# pcb_heater.net
KiCad netlist of a schematic drawn in Altium Designer
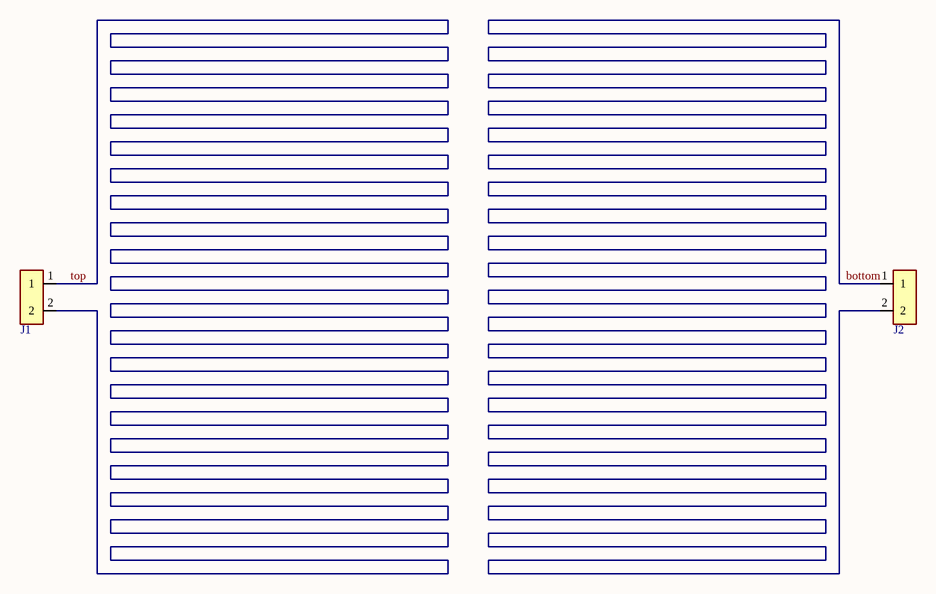
[diagram p0: pcb_heater.SchDoc]

(export (version "E")
  (design (tool "Eeschema 10.0.6"))
  (components
    (comp (ref "J1")
      (value "Connector, PCB heater")
      (footprint "pcb_heater_connector")
      (libsource (lib "") (part "Connector, PCB heater_1"))
    )
    (comp (ref "J2")
      (value "Connector, PCB heater")
      (footprint "pcb_heater_connector")
      (libsource (lib "jclib") (part "Connector, PCB heater"))
    )
  )
  (nets
    (net (code "1") (name "/bottom") (class "Default")
      (node (ref "J2") (pin "1") (pinfunction "1_1") (pintype "passive"))
      (node (ref "J2") (pin "2") (pinfunction "2_2") (pintype "passive"))
    )
    (net (code "2") (name "/top") (class "Default")
      (node (ref "J1") (pin "1") (pinfunction "1_1") (pintype "passive"))
      (node (ref "J1") (pin "2") (pinfunction "2_2") (pintype "passive"))
    )
  )
)
